# StromsensorTP.net
KiCad netlist of a schematic drawn in Altium Designer
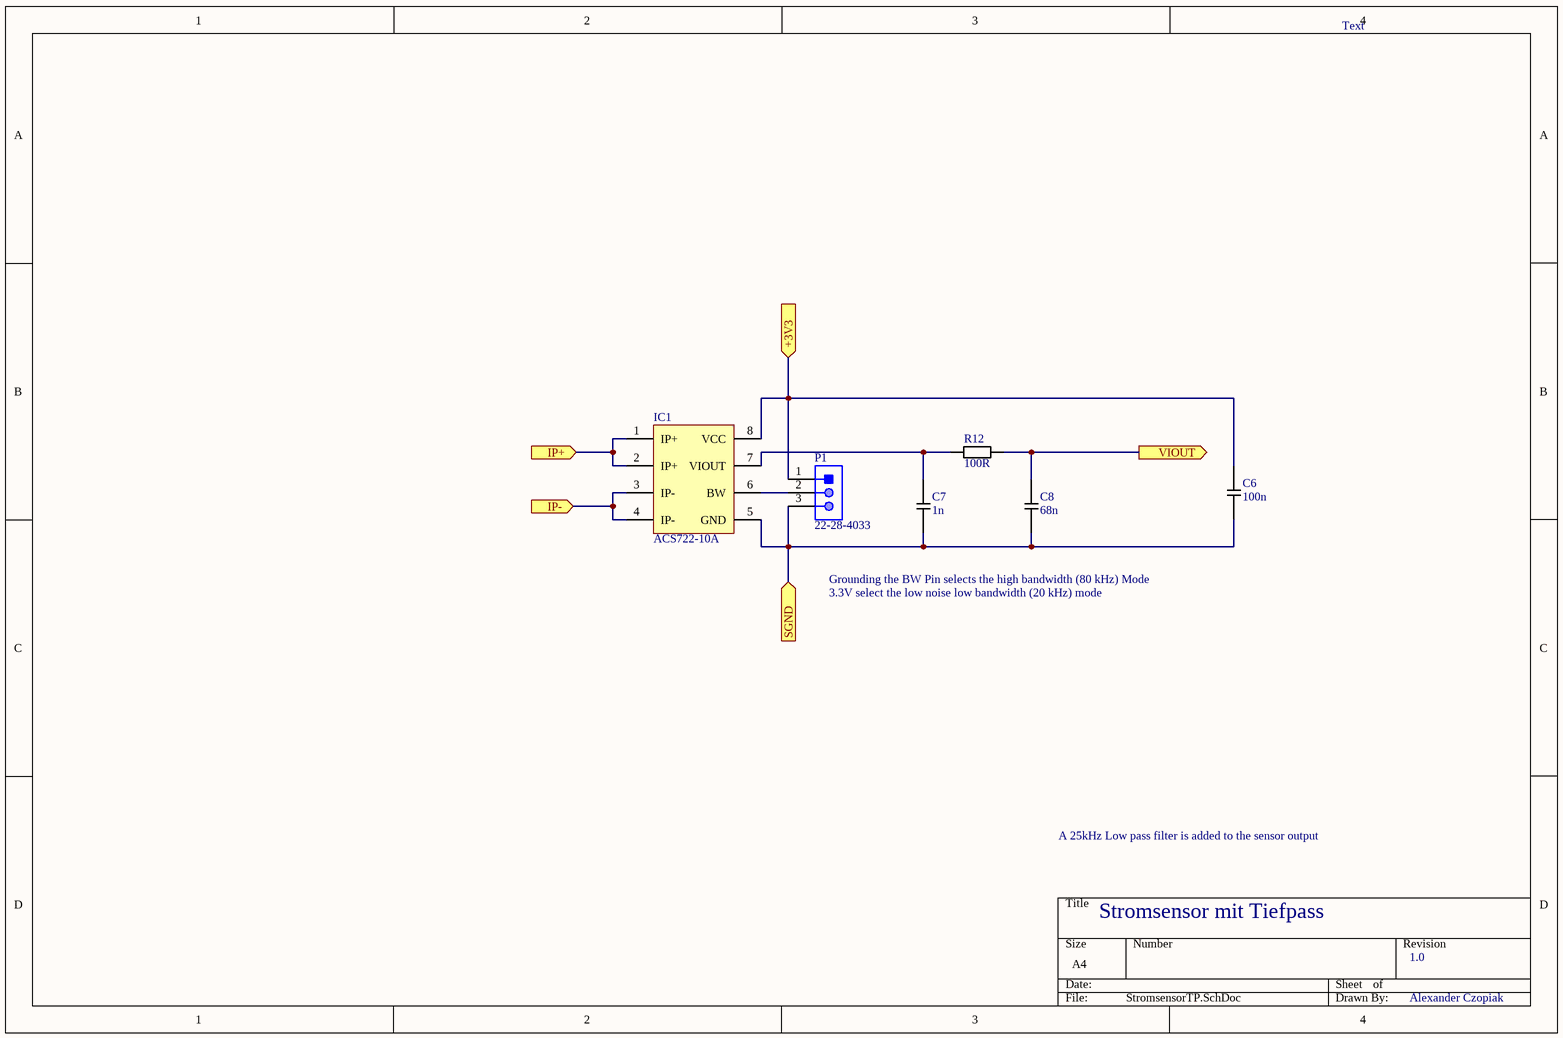
[diagram p0: StromsensorTP.SchDoc]

(export (version "E")
  (design (tool "Eeschema 10.0.6"))
  (components
    (comp (ref "C6")
      (value "100n")
      (footprint "1206_C")
      (description "Kondensator (ohne Polarität)")
      (libsource (lib "HSLS_Parts") (part "CAP"))
    )
    (comp (ref "C7")
      (value "1n")
      (footprint "1206_C")
      (description "Kondensator (ohne Polarität)")
      (libsource (lib "HSLS_Parts") (part "CAP"))
    )
    (comp (ref "C8")
      (value "68n")
      (footprint "1206_C")
      (description "Kondensator (ohne Polarität)")
      (libsource (lib "HSLS_Parts") (part "CAP"))
    )
    (comp (ref "IC1")
      (value "ACS722-10A")
      (footprint "SO08_N")
      (libsource (lib "HSLS_Parts") (part "Current Sensor ACS722"))
    )
    (comp (ref "P1")
      (value "22-28-4033")
      (footprint "MOLX-22-28-4033_V")
      (fields (field (name "MANUFACTURER") "Molex"))
      (libsource (lib "Altium Content Vault") (part "CN-1P-M-R3"))
    )
    (comp (ref "R12")
      (value "100R")
      (footprint "1206_R")
      (description "Widerstand")
      (libsource (lib "HSLS_Parts") (part "WIDERSTAND"))
    )
  )
  (nets
    (net (code "1") (name "/+3V3") (class "Default")
      (node (ref "C6") (pin "2") (pinfunction "2_2") (pintype "passive"))
      (node (ref "IC1") (pin "8") (pinfunction "VCC_8") (pintype "passive"))
      (node (ref "P1") (pin "1") (pinfunction "1_1") (pintype "passive"))
    )
    (net (code "2") (name "/IP+") (class "Default")
      (node (ref "IC1") (pin "1") (pinfunction "IP+_1") (pintype "passive"))
      (node (ref "IC1") (pin "2") (pinfunction "IP+_2") (pintype "passive"))
    )
    (net (code "3") (name "/IP-") (class "Default")
      (node (ref "IC1") (pin "3") (pinfunction "IP-_3") (pintype "passive"))
      (node (ref "IC1") (pin "4") (pinfunction "IP-_4") (pintype "passive"))
    )
    (net (code "4") (name "/SGND") (class "Default")
      (node (ref "C6") (pin "1") (pinfunction "1_1") (pintype "passive"))
      (node (ref "C7") (pin "1") (pinfunction "1_1") (pintype "passive"))
      (node (ref "C8") (pin "1") (pinfunction "1_1") (pintype "passive"))
      (node (ref "IC1") (pin "5") (pinfunction "GND_5") (pintype "passive"))
      (node (ref "P1") (pin "3") (pinfunction "3_3") (pintype "passive"))
    )
    (net (code "5") (name "/VIOUT") (class "Default")
      (node (ref "C8") (pin "2") (pinfunction "2_2") (pintype "passive"))
      (node (ref "R12") (pin "2") (pinfunction "2_2") (pintype "passive"))
    )
    (net (code "6") (name "Net-(IC1-BW)") (class "Default")
      (node (ref "IC1") (pin "6") (pinfunction "BW_6") (pintype "passive"))
      (node (ref "P1") (pin "2") (pinfunction "2_2") (pintype "passive"))
    )
    (net (code "7") (name "Net-(IC1-VIOUT)") (class "Default")
      (node (ref "C7") (pin "2") (pinfunction "2_2") (pintype "passive"))
      (node (ref "IC1") (pin "7") (pinfunction "VIOUT_7") (pintype "passive"))
      (node (ref "R12") (pin "1") (pinfunction "1_1") (pintype "passive"))
    )
  )
)
